# CYAN_EVSE_Logic_board_v1_0.net
KiCad netlist of a schematic drawn in Altium Designer
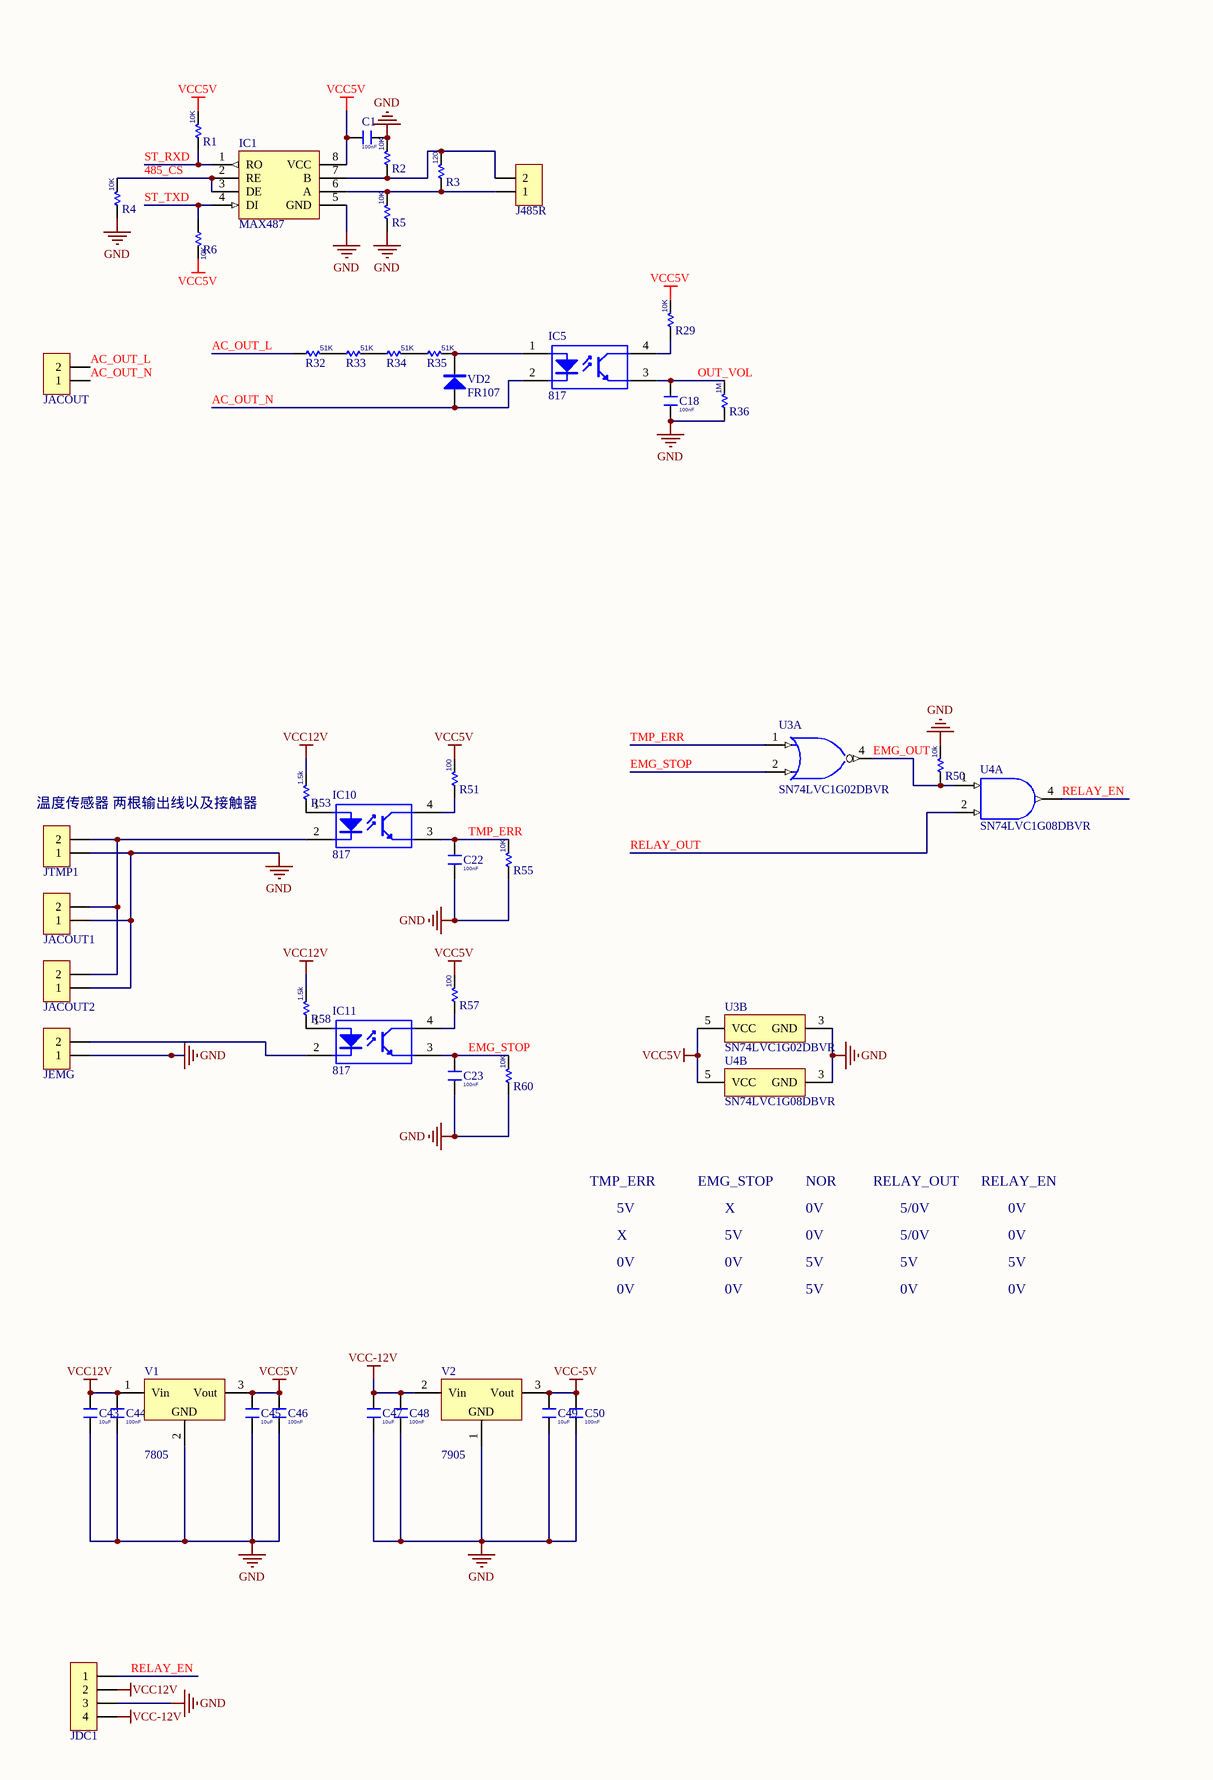
[diagram p0: CYAN_EVSE_Logic_board_v1.0.SchDoc, left]
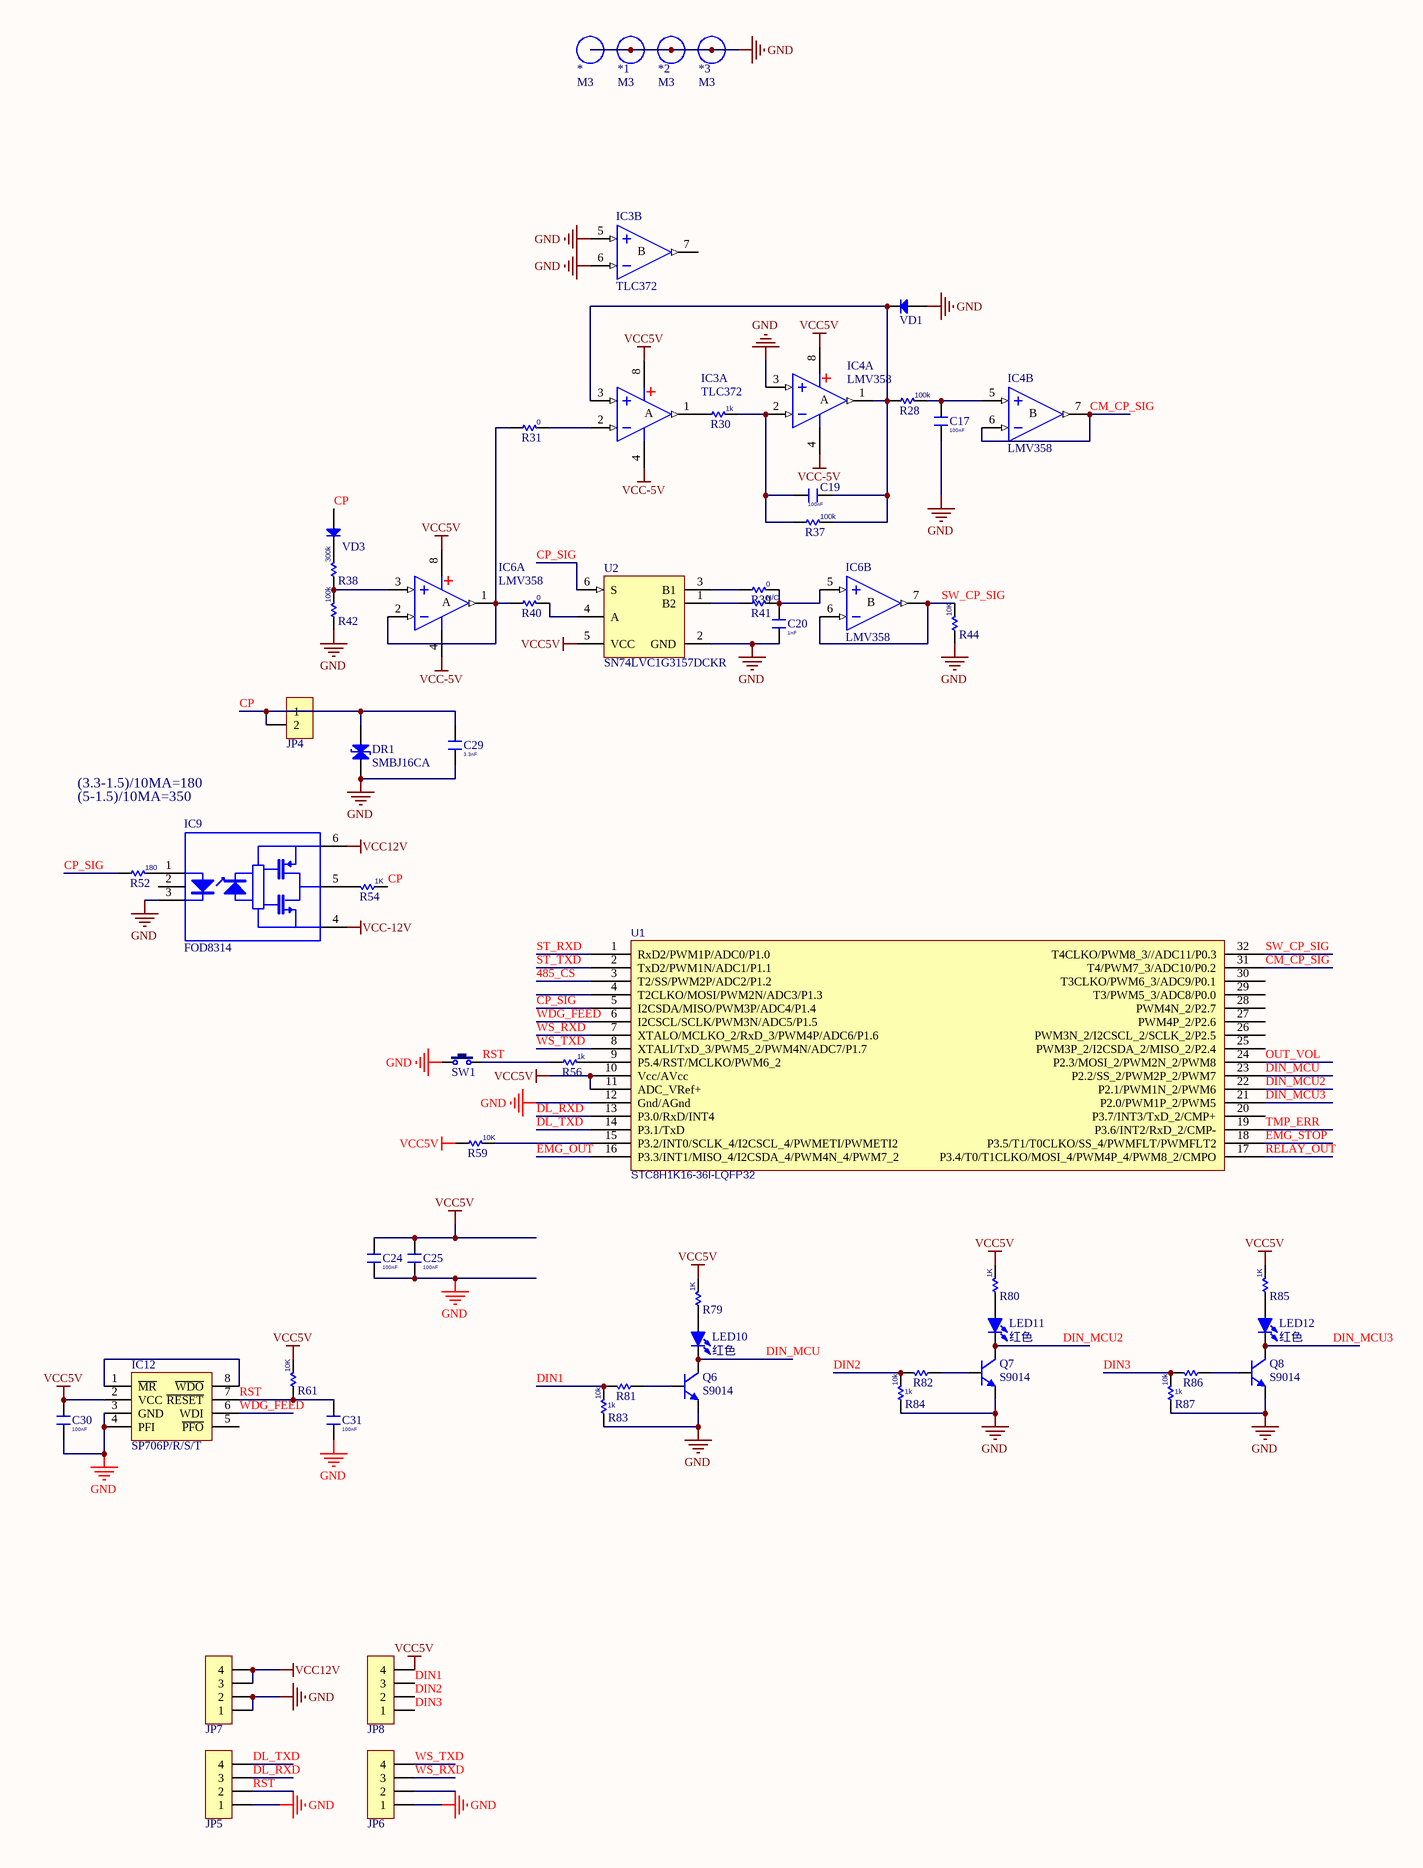
[diagram p1: CYAN_EVSE_Logic_board_v1.0.SchDoc, right]

(export (version "E")
  (design (tool "Eeschema 10.0.6"))
  (components
    (comp (ref "*")
      (value "M3")
      (footprint "M3 125X300")
      (description "铜柱孔")
      (libsource (lib "未分类器件") (part "M3"))
    )
    (comp (ref "*1")
      (value "M3")
      (footprint "M3 125X300")
      (description "铜柱孔")
      (libsource (lib "未分类器件") (part "M3"))
    )
    (comp (ref "*2")
      (value "M3")
      (footprint "M3 125X300")
      (description "铜柱孔")
      (libsource (lib "未分类器件") (part "M3"))
    )
    (comp (ref "*3")
      (value "M3")
      (footprint "M3 125X300")
      (description "铜柱孔")
      (libsource (lib "未分类器件") (part "M3"))
    )
    (comp (ref "C1")
      (value "100nF")
      (footprint "C 0805")
      (description "无极性贴片电容")
      (fields (field (name "VOLTAGE") "20V") (field (name "Comment") "C"))
      (libsource (lib "电阻-电容-电感") (part "C"))
    )
    (comp (ref "C17")
      (value "100nF")
      (footprint "C 0805")
      (description "无极性贴片电容")
      (fields (field (name "VOLTAGE") "20V") (field (name "Comment") "C"))
      (libsource (lib "电阻-电容-电感") (part "C"))
    )
    (comp (ref "C18")
      (value "100nF")
      (footprint "C 0805")
      (description "无极性贴片电容")
      (fields (field (name "VOLTAGE") "20V") (field (name "Comment") "C"))
      (libsource (lib "电阻-电容-电感") (part "C"))
    )
    (comp (ref "C19")
      (value "100nF")
      (footprint "C 0805")
      (description "无极性贴片电容")
      (fields (field (name "VOLTAGE") "20V") (field (name "Comment") "C"))
      (libsource (lib "电阻-电容-电感") (part "C"))
    )
    (comp (ref "C20")
      (value "1nF")
      (footprint "C 0805")
      (description "无极性贴片电容")
      (fields (field (name "VOLTAGE") "20V") (field (name "Comment") "C"))
      (libsource (lib "电阻-电容-电感") (part "C"))
    )
    (comp (ref "C22")
      (value "100nF")
      (footprint "C 0805")
      (description "无极性贴片电容")
      (fields (field (name "VOLTAGE") "20V") (field (name "Comment") "C"))
      (libsource (lib "电阻-电容-电感") (part "C"))
    )
    (comp (ref "C23")
      (value "100nF")
      (footprint "C 0805")
      (description "无极性贴片电容")
      (fields (field (name "VOLTAGE") "20V") (field (name "Comment") "C"))
      (libsource (lib "电阻-电容-电感") (part "C"))
    )
    (comp (ref "C24")
      (value "100nF")
      (footprint "C 0805")
      (description "无极性贴片电容")
      (fields (field (name "VOLTAGE") "20V") (field (name "Comment") "C"))
      (libsource (lib "电阻-电容-电感") (part "C"))
    )
    (comp (ref "C25")
      (value "100nF")
      (footprint "C 0805")
      (description "无极性贴片电容")
      (fields (field (name "VOLTAGE") "20V") (field (name "Comment") "C"))
      (libsource (lib "电阻-电容-电感") (part "C"))
    )
    (comp (ref "C29")
      (value "3.3nF")
      (footprint "C 1206")
      (description "无极性贴片电容")
      (fields (field (name "VOLTAGE") "50V") (field (name "Comment") "C"))
      (libsource (lib "电阻-电容-电感") (part "C"))
    )
    (comp (ref "C30")
      (value "100nF")
      (footprint "C 0805")
      (description "无极性贴片电容")
      (fields (field (name "VOLTAGE") "20V") (field (name "Comment") "C"))
      (libsource (lib "电阻-电容-电感") (part "C"))
    )
    (comp (ref "C31")
      (value "100nF")
      (footprint "C 0805")
      (description "无极性贴片电容")
      (fields (field (name "VOLTAGE") "20V") (field (name "Comment") "C"))
      (libsource (lib "电阻-电容-电感") (part "C"))
    )
    (comp (ref "C43")
      (value "10uF")
      (footprint "C 0805")
      (description "无极性贴片电容")
      (fields (field (name "VOLTAGE") "50V") (field (name "Comment") "C"))
      (libsource (lib "电阻-电容-电感") (part "C"))
    )
    (comp (ref "C44")
      (value "100nF")
      (footprint "C 0805")
      (description "无极性贴片电容")
      (fields (field (name "VOLTAGE") "50V") (field (name "Comment") "C"))
      (libsource (lib "电阻-电容-电感") (part "C"))
    )
    (comp (ref "C45")
      (value "10uF")
      (footprint "C 0805")
      (description "无极性贴片电容")
      (fields (field (name "VOLTAGE") "50V") (field (name "Comment") "C"))
      (libsource (lib "电阻-电容-电感") (part "C"))
    )
    (comp (ref "C46")
      (value "100nF")
      (footprint "C 0805")
      (description "无极性贴片电容")
      (fields (field (name "VOLTAGE") "50V") (field (name "Comment") "C"))
      (libsource (lib "电阻-电容-电感") (part "C"))
    )
    (comp (ref "C47")
      (value "10uF")
      (footprint "C 0805")
      (description "无极性贴片电容")
      (fields (field (name "VOLTAGE") "50V") (field (name "Comment") "C"))
      (libsource (lib "电阻-电容-电感") (part "C"))
    )
    (comp (ref "C48")
      (value "100nF")
      (footprint "C 0805")
      (description "无极性贴片电容")
      (fields (field (name "VOLTAGE") "50V") (field (name "Comment") "C"))
      (libsource (lib "电阻-电容-电感") (part "C"))
    )
    (comp (ref "C49")
      (value "10uF")
      (footprint "C 0805")
      (description "无极性贴片电容")
      (fields (field (name "VOLTAGE") "50V") (field (name "Comment") "C"))
      (libsource (lib "电阻-电容-电感") (part "C"))
    )
    (comp (ref "C50")
      (value "100nF")
      (footprint "C 0805")
      (description "无极性贴片电容")
      (fields (field (name "VOLTAGE") "50V") (field (name "Comment") "C"))
      (libsource (lib "电阻-电容-电感") (part "C"))
    )
    (comp (ref "DR1")
      (value "SMBJ16CA")
      (footprint "SMB")
      (description "瞬态电压抑制二极管")
      (libsource (lib "二极管-整流桥") (part "DR"))
    )
    (comp (ref "IC1")
      (value "MAX487")
      (footprint "SOP8_N")
      (description "RS485总线收发芯片")
      (libsource (lib "IC芯片") (part "MAX487"))
    )
    (comp (ref "IC3")
      (value "TLC372")
      (footprint "SOP8_L")
      (description "双路电压比较,MOS下臂输出")
      (libsource (lib "IC芯片") (part "TLC372"))
    )
    (comp (ref "IC4")
      (value "LMV358")
      (footprint "SOP8_N")
      (description "双路运放")
      (libsource (lib "IC芯片") (part "LM358"))
    )
    (comp (ref "IC5")
      (value "817")
      (footprint "SOP4-W2.54_M")
      (description "线性光耦")
      (libsource (lib "传感元件") (part "817"))
    )
    (comp (ref "IC6")
      (value "LMV358")
      (footprint "SOP8_N")
      (description "双路运放")
      (libsource (lib "IC芯片") (part "LM358"))
    )
    (comp (ref "IC9")
      (value "FOD8314")
      (footprint "SOP6_L")
      (description "MOSFET/IGBT 驱动光耦，15-30v 1a")
      (libsource (lib "传感元件") (part "FOD8314"))
    )
    (comp (ref "IC10")
      (value "817")
      (footprint "SOP4-W2.54_M")
      (description "线性光耦")
      (libsource (lib "传感元件") (part "817"))
    )
    (comp (ref "IC11")
      (value "817")
      (footprint "SOP4-W2.54_M")
      (description "线性光耦")
      (libsource (lib "传感元件") (part "817"))
    )
    (comp (ref "IC12")
      (value "SP706P/R/S/T")
      (footprint "SOP8_N")
      (description "处理器监控芯片")
      (libsource (lib "IC芯片") (part "SP706"))
    )
    (comp (ref "J485R")
      (value "HDR-1X2")
      (footprint "MC 1,5/ 2-G-3,81")
      (description "2P接插件")
      (libsource (lib "接插件") (part "Header 2"))
    )
    (comp (ref "JACOUT")
      (value "HDR-1X2")
      (footprint "MC 1,5/ 2-G-3,81")
      (description "2P接插件")
      (libsource (lib "") (part "Header 2_1"))
    )
    (comp (ref "JACOUT1")
      (value "HDR-1X2")
      (footprint "MC 1,5/ 2-G-3,81")
      (description "2P接插件")
      (libsource (lib "") (part "Header 2_1"))
    )
    (comp (ref "JACOUT2")
      (value "HDR-1X2")
      (footprint "MC 1,5/ 2-G-3,81")
      (description "2P接插件")
      (libsource (lib "") (part "Header 2_1"))
    )
    (comp (ref "JDC1")
      (value "HDR-1X4")
      (footprint "MC 1,5/ 4-G-3,81")
      (description "4P接插件")
      (libsource (lib "") (part "Header 4_1"))
    )
    (comp (ref "JEMG")
      (value "HDR-1X2")
      (footprint "MC 1,5/ 2-G-3,81")
      (description "2P接插件")
      (libsource (lib "") (part "Header 2_1"))
    )
    (comp (ref "JP4")
      (value "HDR-1X2")
      (footprint "MC 1,5/ 2-G-3,81")
      (description "2P接插件")
      (libsource (lib "") (part "Header 2_2"))
    )
    (comp (ref "JP5")
      (value "HDR-1X4")
      (footprint "HDR-1X4")
      (description "4P接插件")
      (libsource (lib "接插件") (part "Header 4"))
    )
    (comp (ref "JP6")
      (value "HDR-1X4")
      (footprint "MC 1,5/ 4-G-3,81")
      (description "4P接插件")
      (libsource (lib "接插件") (part "Header 4"))
    )
    (comp (ref "JP7")
      (value "HDR-1X4")
      (footprint "MC 1,5/ 4-G-3,81")
      (description "4P接插件")
      (libsource (lib "接插件") (part "Header 4"))
    )
    (comp (ref "JP8")
      (value "HDR-1X4")
      (footprint "MC 1,5/ 4-G-3,81")
      (description "4P接插件")
      (libsource (lib "接插件") (part "Header 4"))
    )
    (comp (ref "JTMP1")
      (value "HDR-1X2")
      (footprint "MC 1,5/ 2-G-3,81")
      (description "2P接插件")
      (libsource (lib "") (part "Header 2_1"))
    )
    (comp (ref "LED10")
      (value "红色")
      (footprint "LED 0805G")
      (description "贴片LED")
      (libsource (lib "LED") (part "LED-SMD"))
    )
    (comp (ref "LED11")
      (value "红色")
      (footprint "LED 0805G")
      (description "贴片LED")
      (libsource (lib "LED") (part "LED-SMD"))
    )
    (comp (ref "LED12")
      (value "红色")
      (footprint "LED 0805G")
      (description "贴片LED")
      (libsource (lib "LED") (part "LED-SMD"))
    )
    (comp (ref "Q6")
      (value "S9014")
      (footprint "SOT23-3N")
      (description "低噪放大-NPN型")
      (libsource (lib "三极管") (part "9014-SMD"))
    )
    (comp (ref "Q7")
      (value "S9014")
      (footprint "SOT23-3N")
      (description "低噪放大-NPN型")
      (libsource (lib "三极管") (part "9014-SMD"))
    )
    (comp (ref "Q8")
      (value "S9014")
      (footprint "SOT23-3N")
      (description "低噪放大-NPN型")
      (libsource (lib "三极管") (part "9014-SMD"))
    )
    (comp (ref "R1")
      (value "10K")
      (footprint "R 0805")
      (description "贴片电阻")
      (fields (field (name "Comment") "R"))
      (libsource (lib "电阻-电容-电感") (part "R"))
    )
    (comp (ref "R2")
      (value "10K")
      (footprint "R 0805")
      (description "贴片电阻")
      (fields (field (name "Comment") "R"))
      (libsource (lib "电阻-电容-电感") (part "R"))
    )
    (comp (ref "R3")
      (value "120")
      (footprint "R 1206")
      (description "贴片电阻")
      (fields (field (name "Comment") "R"))
      (libsource (lib "电阻-电容-电感") (part "R"))
    )
    (comp (ref "R4")
      (value "10K")
      (footprint "R 0805")
      (description "贴片电阻")
      (fields (field (name "Comment") "R"))
      (libsource (lib "电阻-电容-电感") (part "R"))
    )
    (comp (ref "R5")
      (value "10K")
      (footprint "R 0805")
      (description "贴片电阻")
      (fields (field (name "Comment") "R"))
      (libsource (lib "电阻-电容-电感") (part "R"))
    )
    (comp (ref "R6")
      (value "10K")
      (footprint "R 0805")
      (description "贴片电阻")
      (fields (field (name "Comment") "R"))
      (libsource (lib "电阻-电容-电感") (part "R"))
    )
    (comp (ref "R28")
      (value "100k")
      (footprint "R 0805")
      (description "贴片电阻")
      (fields (field (name "Comment") "R"))
      (libsource (lib "电阻-电容-电感") (part "R"))
    )
    (comp (ref "R29")
      (value "10K")
      (footprint "R 0805")
      (description "贴片电阻")
      (fields (field (name "Comment") "R"))
      (libsource (lib "电阻-电容-电感") (part "R"))
    )
    (comp (ref "R30")
      (value "1k")
      (footprint "R 0805")
      (description "贴片电阻")
      (fields (field (name "Comment") "R"))
      (libsource (lib "电阻-电容-电感") (part "R"))
    )
    (comp (ref "R31")
      (value "0")
      (footprint "R 0805")
      (description "贴片电阻")
      (fields (field (name "Comment") "R"))
      (libsource (lib "电阻-电容-电感") (part "R"))
    )
    (comp (ref "R32")
      (value "51K")
      (footprint "R 1206")
      (description "贴片电阻")
      (fields (field (name "Comment") "R"))
      (libsource (lib "电阻-电容-电感") (part "R"))
    )
    (comp (ref "R33")
      (value "51K")
      (footprint "R 1206")
      (description "贴片电阻")
      (fields (field (name "Comment") "R"))
      (libsource (lib "电阻-电容-电感") (part "R"))
    )
    (comp (ref "R34")
      (value "51K")
      (footprint "R 1206")
      (description "贴片电阻")
      (fields (field (name "Comment") "R"))
      (libsource (lib "电阻-电容-电感") (part "R"))
    )
    (comp (ref "R35")
      (value "51K")
      (footprint "R 1206")
      (description "贴片电阻")
      (fields (field (name "Comment") "R"))
      (libsource (lib "电阻-电容-电感") (part "R"))
    )
    (comp (ref "R36")
      (value "1M")
      (footprint "R 0805")
      (description "贴片电阻")
      (fields (field (name "Comment") "R"))
      (libsource (lib "电阻-电容-电感") (part "R"))
    )
    (comp (ref "R37")
      (value "100k")
      (footprint "R 0805")
      (description "贴片电阻")
      (fields (field (name "Comment") "R"))
      (libsource (lib "电阻-电容-电感") (part "R"))
    )
    (comp (ref "R38")
      (value "300k")
      (footprint "R 0805")
      (description "贴片电阻")
      (fields (field (name "Comment") "R"))
      (libsource (lib "电阻-电容-电感") (part "R"))
    )
    (comp (ref "R39")
      (value "0")
      (footprint "R 0805")
      (description "贴片电阻")
      (fields (field (name "Comment") "R"))
      (libsource (lib "电阻-电容-电感") (part "R"))
    )
    (comp (ref "R40")
      (value "0")
      (footprint "R 0805")
      (description "贴片电阻")
      (fields (field (name "Comment") "R"))
      (libsource (lib "电阻-电容-电感") (part "R"))
    )
    (comp (ref "R41")
      (value "N/C")
      (footprint "R 0805")
      (description "贴片电阻")
      (fields (field (name "Comment") "R"))
      (libsource (lib "电阻-电容-电感") (part "R"))
    )
    (comp (ref "R42")
      (value "100k")
      (footprint "R 0805")
      (description "贴片电阻")
      (fields (field (name "Comment") "R"))
      (libsource (lib "电阻-电容-电感") (part "R"))
    )
    (comp (ref "R44")
      (value "10K")
      (footprint "R 0805")
      (description "贴片电阻")
      (fields (field (name "Comment") "R"))
      (libsource (lib "电阻-电容-电感") (part "R"))
    )
    (comp (ref "R50")
      (value "10k")
      (footprint "R 0805")
      (description "贴片电阻")
      (fields (field (name "Comment") "R"))
      (libsource (lib "电阻-电容-电感") (part "R"))
    )
    (comp (ref "R51")
      (value "100")
      (footprint "R 0805")
      (description "贴片电阻")
      (fields (field (name "Comment") "R"))
      (libsource (lib "电阻-电容-电感") (part "R"))
    )
    (comp (ref "R52")
      (value "180")
      (footprint "R 0805")
      (description "贴片电阻")
      (fields (field (name "Comment") "R"))
      (libsource (lib "电阻-电容-电感") (part "R"))
    )
    (comp (ref "R53")
      (value "1.5k")
      (footprint "R 0805")
      (description "贴片电阻")
      (fields (field (name "Comment") "R"))
      (libsource (lib "电阻-电容-电感") (part "R"))
    )
    (comp (ref "R54")
      (value "1K")
      (footprint "R 1206")
      (description "贴片电阻")
      (fields (field (name "Comment") "R"))
      (libsource (lib "电阻-电容-电感") (part "R"))
    )
    (comp (ref "R55")
      (value "10K")
      (footprint "R 0805")
      (description "贴片电阻")
      (fields (field (name "Comment") "R"))
      (libsource (lib "电阻-电容-电感") (part "R"))
    )
    (comp (ref "R56")
      (value "1k")
      (footprint "R 0805")
      (description "贴片电阻")
      (fields (field (name "Comment") "R"))
      (libsource (lib "电阻-电容-电感") (part "R"))
    )
    (comp (ref "R57")
      (value "100")
      (footprint "R 0805")
      (description "贴片电阻")
      (fields (field (name "Comment") "R"))
      (libsource (lib "电阻-电容-电感") (part "R"))
    )
    (comp (ref "R58")
      (value "1.5k")
      (footprint "R 0805")
      (description "贴片电阻")
      (fields (field (name "Comment") "R"))
      (libsource (lib "电阻-电容-电感") (part "R"))
    )
    (comp (ref "R59")
      (value "10K")
      (footprint "R 0805")
      (description "贴片电阻")
      (fields (field (name "Comment") "R"))
      (libsource (lib "电阻-电容-电感") (part "R"))
    )
    (comp (ref "R60")
      (value "10K")
      (footprint "R 0805")
      (description "贴片电阻")
      (fields (field (name "Comment") "R"))
      (libsource (lib "电阻-电容-电感") (part "R"))
    )
    (comp (ref "R61")
      (value "10K")
      (footprint "R 0805")
      (description "贴片电阻")
      (fields (field (name "Comment") "R"))
      (libsource (lib "电阻-电容-电感") (part "R"))
    )
    (comp (ref "R79")
      (value "1K")
      (footprint "R 0805")
      (description "贴片电阻")
      (fields (field (name "Comment") "R"))
      (libsource (lib "电阻-电容-电感") (part "R"))
    )
    (comp (ref "R80")
      (value "1K")
      (footprint "R 0805")
      (description "贴片电阻")
      (fields (field (name "Comment") "R"))
      (libsource (lib "电阻-电容-电感") (part "R"))
    )
    (comp (ref "R81")
      (value "1k")
      (footprint "R 0805")
      (description "贴片电阻")
      (fields (field (name "Comment") "R"))
      (libsource (lib "电阻-电容-电感") (part "R"))
    )
    (comp (ref "R82")
      (value "1k")
      (footprint "R 0805")
      (description "贴片电阻")
      (fields (field (name "Comment") "R"))
      (libsource (lib "电阻-电容-电感") (part "R"))
    )
    (comp (ref "R83")
      (value "10k")
      (footprint "R 0805")
      (description "贴片电阻")
      (fields (field (name "Comment") "R"))
      (libsource (lib "电阻-电容-电感") (part "R"))
    )
    (comp (ref "R84")
      (value "10k")
      (footprint "R 0805")
      (description "贴片电阻")
      (fields (field (name "Comment") "R"))
      (libsource (lib "电阻-电容-电感") (part "R"))
    )
    (comp (ref "R85")
      (value "1K")
      (footprint "R 0805")
      (description "贴片电阻")
      (fields (field (name "Comment") "R"))
      (libsource (lib "电阻-电容-电感") (part "R"))
    )
    (comp (ref "R86")
      (value "1k")
      (footprint "R 0805")
      (description "贴片电阻")
      (fields (field (name "Comment") "R"))
      (libsource (lib "电阻-电容-电感") (part "R"))
    )
    (comp (ref "R87")
      (value "10k")
      (footprint "R 0805")
      (description "贴片电阻")
      (fields (field (name "Comment") "R"))
      (libsource (lib "电阻-电容-电感") (part "R"))
    )
    (comp (ref "SW1") (value "NC") (footprint "TSW SMD-3*6*2.5") (libsource (lib "按键-开关") (part "TSW 3x6")))
    (comp (ref "U1")
      (value "STC8H1K16-36I-LQFP32")
      (footprint "LQFP32 7X7_N")
      (libsource (lib "STC系列单片机") (part "STC8H1K16-36I-LQFP32"))
    )
    (comp (ref "U2")
      (value "SN74LVC1G3157DCKR")
      (footprint "DCK0006A_N")
      (description "Single-Pole, Double-Throw Analog Switch, DCK0006A, LARGE T&R")
      (fields
        (field (name "GENERIC PART NUMBER") "SN74LVC1G3157")
        (field (name "MANUFACTURER") "Texas Instruments")
      )
      (libsource (lib "TI_Logic_Little_Logic") (part "SN74LVC1G3157DCKR"))
    )
    (comp (ref "U3")
      (value "SN74LVC1G02DBVR")
      (footprint "DBV0005A_N")
      (description "Single 2-Input Positive-NOR Gate, DBV0005A, LARGE T&R")
      (fields
        (field (name "GENERIC PART NUMBER") "SN74LVC1G02")
        (field (name "MANUFACTURER") "Texas Instruments")
      )
      (libsource (lib "TI_Logic_Little_Logic") (part "SN74LVC1G02DBVR"))
    )
    (comp (ref "U4")
      (value "SN74LVC1G08DBVR")
      (footprint "DBV0005A_N")
      (description "Single 2-Input Positive-AND Gate, DBV0005A, LARGE T&R")
      (fields
        (field (name "GENERIC PART NUMBER") "SN74LVC1G08")
        (field (name "MANUFACTURER") "Texas Instruments")
      )
      (libsource (lib "TI_Logic_Little_Logic") (part "SN74LVC1G08DBVR"))
    )
    (comp (ref "V1")
      (value "7805")
      (footprint "TO252")
      (description "线性稳压芯片")
      (libsource (lib "IC芯片") (part "78xx"))
    )
    (comp (ref "V2")
      (value "7905")
      (footprint "TO252")
      (description "线性稳压芯片")
      (libsource (lib "IC芯片") (part "79xx"))
    )
    (comp (ref "VD1")
      (value "1N4148")
      (footprint "SOD-323")
      (description "高速开关二极管")
      (libsource (lib "二极管-整流桥") (part "1N4148"))
    )
    (comp (ref "VD2")
      (value "FR107")
      (footprint "SOD-123")
      (description "快恢复整流二极管")
      (libsource (lib "二极管-整流桥") (part "FR107"))
    )
    (comp (ref "VD3")
      (value "1N4148")
      (footprint "SOD-323")
      (description "高速开关二极管")
      (libsource (lib "二极管-整流桥") (part "1N4148"))
    )
  )
  (nets
    (net (code "1") (name "/485_CS") (class "Default")
      (node (ref "IC1") (pin "2") (pinfunction "RE_2") (pintype "passive"))
      (node (ref "IC1") (pin "3") (pinfunction "DE_3") (pintype "passive"))
      (node (ref "R4") (pin "2") (pinfunction "2_2") (pintype "passive"))
      (node (ref "U1") (pin "3") (pinfunction "T2/SS/PWM2P/ADC2/P1.2_3") (pintype "passive"))
    )
    (net (code "2") (name "/AC_OUT_L") (class "Default")
      (node (ref "JACOUT") (pin "2") (pinfunction "2_2") (pintype "passive"))
      (node (ref "R32") (pin "1") (pinfunction "1_1") (pintype "passive"))
    )
    (net (code "3") (name "/AC_OUT_N") (class "Default")
      (node (ref "IC5") (pin "2") (pinfunction "K_2") (pintype "passive"))
      (node (ref "JACOUT") (pin "1") (pinfunction "1_1") (pintype "passive"))
      (node (ref "VD2") (pin "1") (pinfunction "A_1") (pintype "passive"))
    )
    (net (code "4") (name "/CM_CP_SIG") (class "Default")
      (node (ref "IC4") (pin "6") (pinfunction "IN-_6") (pintype "input"))
      (node (ref "IC4") (pin "7") (pinfunction "OUT_7") (pintype "output"))
      (node (ref "U1") (pin "31") (pinfunction "T4/PWM7_3/ADC10/P0.2_31") (pintype "passive"))
    )
    (net (code "5") (name "/CP") (class "Default")
      (node (ref "C29") (pin "2") (pinfunction "2_2") (pintype "passive"))
      (node (ref "DR1") (pin "1") (pinfunction "A_1") (pintype "passive"))
      (node (ref "JP4") (pin "1") (pinfunction "1_1") (pintype "passive"))
      (node (ref "JP4") (pin "2") (pinfunction "2_2") (pintype "passive"))
      (node (ref "R54") (pin "1") (pinfunction "1_1") (pintype "passive"))
      (node (ref "VD3") (pin "1") (pinfunction "A_1") (pintype "passive"))
    )
    (net (code "6") (name "/CP_SIG") (class "Default")
      (node (ref "R52") (pin "1") (pinfunction "1_1") (pintype "passive"))
      (node (ref "U1") (pin "5") (pinfunction "I2CSDA/MISO/PWM3P/ADC4/P1.4_5") (pintype "passive"))
      (node (ref "U2") (pin "6") (pinfunction "S_6") (pintype "input"))
    )
    (net (code "7") (name "/DIN1") (class "Default")
      (node (ref "JP8") (pin "3") (pinfunction "3_3") (pintype "passive"))
      (node (ref "R81") (pin "2") (pinfunction "2_2") (pintype "passive"))
      (node (ref "R83") (pin "2") (pinfunction "2_2") (pintype "passive"))
    )
    (net (code "8") (name "/DIN2") (class "Default")
      (node (ref "JP8") (pin "2") (pinfunction "2_2") (pintype "passive"))
      (node (ref "R82") (pin "2") (pinfunction "2_2") (pintype "passive"))
      (node (ref "R84") (pin "2") (pinfunction "2_2") (pintype "passive"))
    )
    (net (code "9") (name "/DIN3") (class "Default")
      (node (ref "JP8") (pin "1") (pinfunction "1_1") (pintype "passive"))
      (node (ref "R86") (pin "2") (pinfunction "2_2") (pintype "passive"))
      (node (ref "R87") (pin "2") (pinfunction "2_2") (pintype "passive"))
    )
    (net (code "10") (name "/DIN_MCU") (class "Default")
      (node (ref "LED10") (pin "2") (pinfunction "K_2") (pintype "passive"))
      (node (ref "Q6") (pin "3") (pinfunction "C_3") (pintype "passive"))
      (node (ref "U1") (pin "23") (pinfunction "P2.2/SS_2/PWM2P_2/PWM7_23") (pintype "passive"))
    )
    (net (code "11") (name "/DIN_MCU2") (class "Default")
      (node (ref "LED11") (pin "2") (pinfunction "K_2") (pintype "passive"))
      (node (ref "Q7") (pin "3") (pinfunction "C_3") (pintype "passive"))
      (node (ref "U1") (pin "22") (pinfunction "P2.1/PWM1N_2/PWM6_22") (pintype "passive"))
    )
    (net (code "12") (name "/DIN_MCU3") (class "Default")
      (node (ref "LED12") (pin "2") (pinfunction "K_2") (pintype "passive"))
      (node (ref "Q8") (pin "3") (pinfunction "C_3") (pintype "passive"))
      (node (ref "U1") (pin "21") (pinfunction "P2.0/PWM1P_2/PWM5_21") (pintype "passive"))
    )
    (net (code "13") (name "/DL_RXD") (class "Default")
      (node (ref "JP5") (pin "3") (pinfunction "3_3") (pintype "passive"))
      (node (ref "U1") (pin "13") (pinfunction "P3.0/RxD/INT4_13") (pintype "passive"))
    )
    (net (code "14") (name "/DL_TXD") (class "Default")
      (node (ref "JP5") (pin "4") (pinfunction "4_4") (pintype "passive"))
      (node (ref "U1") (pin "14") (pinfunction "P3.1/TxD_14") (pintype "passive"))
    )
    (net (code "15") (name "/EMG_OUT") (class "Default")
      (node (ref "R50") (pin "1") (pinfunction "1_1") (pintype "passive"))
      (node (ref "U1") (pin "16") (pinfunction "P3.3/INT1/MISO_4/I2CSDA_4/PWM4N_4/PWM7_2_16") (pintype "passive"))
      (node (ref "U3") (pin "4") (pinfunction "Y_4") (pintype "output"))
      (node (ref "U4") (pin "1") (pinfunction "A_1") (pintype "input"))
    )
    (net (code "16") (name "/EMG_STOP") (class "Default")
      (node (ref "C23") (pin "2") (pinfunction "2_2") (pintype "passive"))
      (node (ref "IC11") (pin "3") (pinfunction "E_3") (pintype "passive"))
      (node (ref "R60") (pin "2") (pinfunction "2_2") (pintype "passive"))
      (node (ref "U1") (pin "18") (pinfunction "P3.5/T1/T0CLKO/SS_4/PWMFLT/PWMFLT2_18") (pintype "passive"))
      (node (ref "U3") (pin "2") (pinfunction "B_2") (pintype "input"))
    )
    (net (code "17") (name "/OUT_VOL") (class "Default")
      (node (ref "C18") (pin "2") (pinfunction "2_2") (pintype "passive"))
      (node (ref "IC5") (pin "3") (pinfunction "E_3") (pintype "passive"))
      (node (ref "R36") (pin "2") (pinfunction "2_2") (pintype "passive"))
      (node (ref "U1") (pin "24") (pinfunction "P2.3/MOSI_2/PWM2N_2/PWM8_24") (pintype "passive"))
    )
    (net (code "18") (name "/RELAY_EN") (class "Default")
      (node (ref "JDC1") (pin "1") (pinfunction "1_1") (pintype "passive"))
      (node (ref "U4") (pin "4") (pinfunction "Y_4") (pintype "output"))
    )
    (net (code "19") (name "/RELAY_OUT") (class "Default")
      (node (ref "U1") (pin "17") (pinfunction "P3.4/T0/T1CLKO/MOSI_4/PWM4P_4/PWM8_2/CMPO_17") (pintype "passive"))
      (node (ref "U4") (pin "2") (pinfunction "B_2") (pintype "input"))
    )
    (net (code "20") (name "/RST") (class "Default")
      (node (ref "C31") (pin "2") (pinfunction "2_2") (pintype "passive"))
      (node (ref "IC12") (pin "7") (pinfunction "~{RESET}_7") (pintype "passive"))
      (node (ref "JP5") (pin "2") (pinfunction "2_2") (pintype "passive"))
      (node (ref "R56") (pin "1") (pinfunction "1_1") (pintype "passive"))
      (node (ref "R61") (pin "1") (pinfunction "1_1") (pintype "passive"))
      (node (ref "SW1") (pin "2") (pinfunction "2_2") (pintype "passive"))
    )
    (net (code "21") (name "/ST_RXD") (class "Default")
      (node (ref "IC1") (pin "1") (pinfunction "RO_1") (pintype "output"))
      (node (ref "R1") (pin "1") (pinfunction "1_1") (pintype "passive"))
      (node (ref "U1") (pin "1") (pinfunction "RxD2/PWM1P/ADC0/P1.0_1") (pintype "passive"))
    )
    (net (code "22") (name "/ST_TXD") (class "Default")
      (node (ref "IC1") (pin "4") (pinfunction "DI_4") (pintype "input"))
      (node (ref "R6") (pin "1") (pinfunction "1_1") (pintype "passive"))
      (node (ref "U1") (pin "2") (pinfunction "TxD2/PWM1N/ADC1/P1.1_2") (pintype "passive"))
    )
    (net (code "23") (name "/SW_CP_SIG") (class "Default")
      (node (ref "IC6") (pin "6") (pinfunction "IN-_6") (pintype "input"))
      (node (ref "IC6") (pin "7") (pinfunction "OUT_7") (pintype "output"))
      (node (ref "R44") (pin "2") (pinfunction "2_2") (pintype "passive"))
      (node (ref "U1") (pin "32") (pinfunction "T4CLKO/PWM8_3//ADC11/P0.3_32") (pintype "passive"))
    )
    (net (code "24") (name "/TMP_ERR") (class "Default")
      (node (ref "C22") (pin "2") (pinfunction "2_2") (pintype "passive"))
      (node (ref "IC10") (pin "3") (pinfunction "E_3") (pintype "passive"))
      (node (ref "R55") (pin "2") (pinfunction "2_2") (pintype "passive"))
      (node (ref "U1") (pin "19") (pinfunction "P3.6/INT2/RxD_2/CMP-_19") (pintype "passive"))
      (node (ref "U3") (pin "1") (pinfunction "A_1") (pintype "input"))
    )
    (net (code "25") (name "/WDG_FEED") (class "Default")
      (node (ref "IC12") (pin "6") (pinfunction "WDI_6") (pintype "passive"))
      (node (ref "U1") (pin "6") (pinfunction "I2CSCL/SCLK/PWM3N/ADC5/P1.5_6") (pintype "passive"))
    )
    (net (code "26") (name "/WS_RXD") (class "Default")
      (node (ref "JP6") (pin "3") (pinfunction "3_3") (pintype "passive"))
      (node (ref "U1") (pin "7") (pinfunction "XTALO/MCLKO_2/RxD_3/PWM4P/ADC6/P1.6_7") (pintype "passive"))
    )
    (net (code "27") (name "/WS_TXD") (class "Default")
      (node (ref "JP6") (pin "4") (pinfunction "4_4") (pintype "passive"))
      (node (ref "U1") (pin "8") (pinfunction "XTALI/TxD_3/PWM5_2/PWM4N/ADC7/P1.7_8") (pintype "passive"))
    )
    (net (code "28") (name "GND") (class "Default")
      (node (ref "*") (pin "0") (pinfunction "0_0") (pintype "passive"))
      (node (ref "*1") (pin "0") (pinfunction "0_0") (pintype "passive"))
      (node (ref "*2") (pin "0") (pinfunction "0_0") (pintype "passive"))
      (node (ref "*3") (pin "0") (pinfunction "0_0") (pintype "passive"))
      (node (ref "C1") (pin "1") (pinfunction "1_1") (pintype "passive"))
      (node (ref "C17") (pin "2") (pinfunction "2_2") (pintype "passive"))
      (node (ref "C18") (pin "1") (pinfunction "1_1") (pintype "passive"))
      (node (ref "C20") (pin "1") (pinfunction "1_1") (pintype "passive"))
      (node (ref "C22") (pin "1") (pinfunction "1_1") (pintype "passive"))
      (node (ref "C23") (pin "1") (pinfunction "1_1") (pintype "passive"))
      (node (ref "C24") (pin "1") (pinfunction "1_1") (pintype "passive"))
      (node (ref "C25") (pin "1") (pinfunction "1_1") (pintype "passive"))
      (node (ref "C29") (pin "1") (pinfunction "1_1") (pintype "passive"))
      (node (ref "C30") (pin "1") (pinfunction "1_1") (pintype "passive"))
      (node (ref "C31") (pin "1") (pinfunction "1_1") (pintype "passive"))
      (node (ref "C43") (pin "1") (pinfunction "1_1") (pintype "passive"))
      (node (ref "C44") (pin "1") (pinfunction "1_1") (pintype "passive"))
      (node (ref "C45") (pin "1") (pinfunction "1_1") (pintype "passive"))
      (node (ref "C46") (pin "1") (pinfunction "1_1") (pintype "passive"))
      (node (ref "C47") (pin "1") (pinfunction "1_1") (pintype "passive"))
      (node (ref "C48") (pin "1") (pinfunction "1_1") (pintype "passive"))
      (node (ref "C49") (pin "1") (pinfunction "1_1") (pintype "passive"))
      (node (ref "C50") (pin "1") (pinfunction "1_1") (pintype "passive"))
      (node (ref "DR1") (pin "2") (pinfunction "K_2") (pintype "passive"))
      (node (ref "IC1") (pin "5") (pinfunction "GND_5") (pintype "passive"))
      (node (ref "IC12") (pin "3") (pinfunction "GND_3") (pintype "passive"))
      (node (ref "IC12") (pin "4") (pinfunction "PFI_4") (pintype "passive"))
      (node (ref "IC3") (pin "5") (pinfunction "IN+_5") (pintype "input"))
      (node (ref "IC3") (pin "6") (pinfunction "IN-_6") (pintype "input"))
      (node (ref "IC4") (pin "3") (pinfunction "IN+_3") (pintype "input"))
      (node (ref "IC9") (pin "3") (pinfunction "K_3") (pintype "passive"))
      (node (ref "JACOUT1") (pin "1") (pinfunction "1_1") (pintype "passive"))
      (node (ref "JACOUT2") (pin "1") (pinfunction "1_1") (pintype "passive"))
      (node (ref "JDC1") (pin "3") (pinfunction "3_3") (pintype "passive"))
      (node (ref "JEMG") (pin "1") (pinfunction "1_1") (pintype "passive"))
      (node (ref "JP5") (pin "1") (pinfunction "1_1") (pintype "passive"))
      (node (ref "JP6") (pin "1") (pinfunction "1_1") (pintype "passive"))
      (node (ref "JP7") (pin "1") (pinfunction "1_1") (pintype "passive"))
      (node (ref "JP7") (pin "2") (pinfunction "2_2") (pintype "passive"))
      (node (ref "JTMP1") (pin "1") (pinfunction "1_1") (pintype "passive"))
      (node (ref "Q6") (pin "2") (pinfunction "E_2") (pintype "passive"))
      (node (ref "Q7") (pin "2") (pinfunction "E_2") (pintype "passive"))
      (node (ref "Q8") (pin "2") (pinfunction "E_2") (pintype "passive"))
      (node (ref "R2") (pin "2") (pinfunction "2_2") (pintype "passive"))
      (node (ref "R36") (pin "1") (pinfunction "1_1") (pintype "passive"))
      (node (ref "R4") (pin "1") (pinfunction "1_1") (pintype "passive"))
      (node (ref "R42") (pin "1") (pinfunction "1_1") (pintype "passive"))
      (node (ref "R44") (pin "1") (pinfunction "1_1") (pintype "passive"))
      (node (ref "R5") (pin "1") (pinfunction "1_1") (pintype "passive"))
      (node (ref "R50") (pin "2") (pinfunction "2_2") (pintype "passive"))
      (node (ref "R55") (pin "1") (pinfunction "1_1") (pintype "passive"))
      (node (ref "R60") (pin "1") (pinfunction "1_1") (pintype "passive"))
      (node (ref "R83") (pin "1") (pinfunction "1_1") (pintype "passive"))
      (node (ref "R84") (pin "1") (pinfunction "1_1") (pintype "passive"))
      (node (ref "R87") (pin "1") (pinfunction "1_1") (pintype "passive"))
      (node (ref "SW1") (pin "1") (pinfunction "1_1") (pintype "passive"))
      (node (ref "U1") (pin "12") (pinfunction "Gnd/AGnd_12") (pintype "passive"))
      (node (ref "U2") (pin "2") (pinfunction "GND_2") (pintype "power_in"))
      (node (ref "U3") (pin "3") (pinfunction "GND_3") (pintype "power_in"))
      (node (ref "U4") (pin "3") (pinfunction "GND_3") (pintype "power_in"))
      (node (ref "V1") (pin "2") (pinfunction "GND_2") (pintype "passive"))
      (node (ref "V2") (pin "1") (pinfunction "GND_1") (pintype "passive"))
      (node (ref "VD1") (pin "1") (pinfunction "A_1") (pintype "passive"))
    )
    (net (code "29") (name "Net-(IC1-A)") (class "Default")
      (node (ref "IC1") (pin "6") (pinfunction "A_6") (pintype "passive"))
      (node (ref "J485R") (pin "1") (pinfunction "1_1") (pintype "passive"))
      (node (ref "R3") (pin "1") (pinfunction "1_1") (pintype "passive"))
      (node (ref "R5") (pin "2") (pinfunction "2_2") (pintype "passive"))
    )
    (net (code "30") (name "Net-(IC1-B)") (class "Default")
      (node (ref "IC1") (pin "7") (pinfunction "B_7") (pintype "passive"))
      (node (ref "J485R") (pin "2") (pinfunction "2_2") (pintype "passive"))
      (node (ref "R2") (pin "1") (pinfunction "1_1") (pintype "passive"))
      (node (ref "R3") (pin "2") (pinfunction "2_2") (pintype "passive"))
    )
    (net (code "31") (name "Net-(IC3A-IN+)") (class "Default")
      (node (ref "C19") (pin "1") (pinfunction "1_1") (pintype "passive"))
      (node (ref "IC3") (pin "3") (pinfunction "IN+_3") (pintype "input"))
      (node (ref "IC4") (pin "1") (pinfunction "OUT_1") (pintype "output"))
      (node (ref "R28") (pin "1") (pinfunction "1_1") (pintype "passive"))
      (node (ref "R37") (pin "2") (pinfunction "2_2") (pintype "passive"))
      (node (ref "VD1") (pin "2") (pinfunction "K_2") (pintype "passive"))
    )
    (net (code "32") (name "Net-(IC3A-IN-)") (class "Default")
      (node (ref "IC3") (pin "2") (pinfunction "IN-_2") (pintype "input"))
      (node (ref "R31") (pin "2") (pinfunction "2_2") (pintype "passive"))
    )
    (net (code "33") (name "Net-(IC3A-OUT)") (class "Default")
      (node (ref "IC3") (pin "1") (pinfunction "OUT_1") (pintype "output"))
      (node (ref "R30") (pin "1") (pinfunction "1_1") (pintype "passive"))
    )
    (net (code "34") (name "Net-(IC4A-IN-)") (class "Default")
      (node (ref "C19") (pin "2") (pinfunction "2_2") (pintype "passive"))
      (node (ref "IC4") (pin "2") (pinfunction "IN-_2") (pintype "input"))
      (node (ref "R30") (pin "2") (pinfunction "2_2") (pintype "passive"))
      (node (ref "R37") (pin "1") (pinfunction "1_1") (pintype "passive"))
    )
    (net (code "35") (name "Net-(IC4B-IN+)") (class "Default")
      (node (ref "C17") (pin "1") (pinfunction "1_1") (pintype "passive"))
      (node (ref "IC4") (pin "5") (pinfunction "IN+_5") (pintype "input"))
      (node (ref "R28") (pin "2") (pinfunction "2_2") (pintype "passive"))
    )
    (net (code "36") (name "Net-(IC5-A)") (class "Default")
      (node (ref "IC5") (pin "1") (pinfunction "A_1") (pintype "passive"))
      (node (ref "R35") (pin "2") (pinfunction "2_2") (pintype "passive"))
      (node (ref "VD2") (pin "2") (pinfunction "K_2") (pintype "passive"))
    )
    (net (code "37") (name "Net-(IC5-C)") (class "Default")
      (node (ref "IC5") (pin "4") (pinfunction "C_4") (pintype "passive"))
      (node (ref "R29") (pin "1") (pinfunction "1_1") (pintype "passive"))
    )
    (net (code "38") (name "Net-(IC6A-IN+)") (class "Default")
      (node (ref "IC6") (pin "3") (pinfunction "IN+_3") (pintype "input"))
      (node (ref "R38") (pin "1") (pinfunction "1_1") (pintype "passive"))
      (node (ref "R42") (pin "2") (pinfunction "2_2") (pintype "passive"))
    )
    (net (code "39") (name "Net-(IC6A-IN-)") (class "Default")
      (node (ref "IC6") (pin "1") (pinfunction "OUT_1") (pintype "output"))
      (node (ref "IC6") (pin "2") (pinfunction "IN-_2") (pintype "input"))
      (node (ref "R31") (pin "1") (pinfunction "1_1") (pintype "passive"))
      (node (ref "R40") (pin "1") (pinfunction "1_1") (pintype "passive"))
    )
    (net (code "40") (name "Net-(IC6B-IN+)") (class "Default")
      (node (ref "C20") (pin "2") (pinfunction "2_2") (pintype "passive"))
      (node (ref "IC6") (pin "5") (pinfunction "IN+_5") (pintype "input"))
      (node (ref "R39") (pin "2") (pinfunction "2_2") (pintype "passive"))
      (node (ref "R41") (pin "2") (pinfunction "2_2") (pintype "passive"))
    )
    (net (code "41") (name "Net-(IC9-A)") (class "Default")
      (node (ref "IC9") (pin "1") (pinfunction "A_1") (pintype "passive"))
      (node (ref "R52") (pin "2") (pinfunction "2_2") (pintype "passive"))
    )
    (net (code "42") (name "Net-(IC9-OUT)") (class "Default")
      (node (ref "IC9") (pin "5") (pinfunction "OUT_5") (pintype "passive"))
      (node (ref "R54") (pin "2") (pinfunction "2_2") (pintype "passive"))
    )
    (net (code "43") (name "Net-(IC10-A)") (class "Default")
      (node (ref "IC10") (pin "1") (pinfunction "A_1") (pintype "passive"))
      (node (ref "R53") (pin "1") (pinfunction "1_1") (pintype "passive"))
    )
    (net (code "44") (name "Net-(IC10-C)") (class "Default")
      (node (ref "IC10") (pin "4") (pinfunction "C_4") (pintype "passive"))
      (node (ref "R51") (pin "1") (pinfunction "1_1") (pintype "passive"))
    )
    (net (code "45") (name "Net-(IC10-K)") (class "Default")
      (node (ref "IC10") (pin "2") (pinfunction "K_2") (pintype "passive"))
      (node (ref "JACOUT1") (pin "2") (pinfunction "2_2") (pintype "passive"))
      (node (ref "JACOUT2") (pin "2") (pinfunction "2_2") (pintype "passive"))
      (node (ref "JTMP1") (pin "2") (pinfunction "2_2") (pintype "passive"))
    )
    (net (code "46") (name "Net-(IC11-A)") (class "Default")
      (node (ref "IC11") (pin "1") (pinfunction "A_1") (pintype "passive"))
      (node (ref "R58") (pin "1") (pinfunction "1_1") (pintype "passive"))
    )
    (net (code "47") (name "Net-(IC11-C)") (class "Default")
      (node (ref "IC11") (pin "4") (pinfunction "C_4") (pintype "passive"))
      (node (ref "R57") (pin "1") (pinfunction "1_1") (pintype "passive"))
    )
    (net (code "48") (name "Net-(IC11-K)") (class "Default")
      (node (ref "IC11") (pin "2") (pinfunction "K_2") (pintype "passive"))
      (node (ref "JEMG") (pin "2") (pinfunction "2_2") (pintype "passive"))
    )
    (net (code "49") (name "Net-(IC12-~{MR})") (class "Default")
      (node (ref "IC12") (pin "1") (pinfunction "~{MR}_1") (pintype "passive"))
      (node (ref "IC12") (pin "8") (pinfunction "~{WDO}_8") (pintype "passive"))
    )
    (net (code "50") (name "Net-(LED10-A)") (class "Default")
      (node (ref "LED10") (pin "1") (pinfunction "A_1") (pintype "passive"))
      (node (ref "R79") (pin "1") (pinfunction "1_1") (pintype "passive"))
    )
    (net (code "51") (name "Net-(LED11-A)") (class "Default")
      (node (ref "LED11") (pin "1") (pinfunction "A_1") (pintype "passive"))
      (node (ref "R80") (pin "1") (pinfunction "1_1") (pintype "passive"))
    )
    (net (code "52") (name "Net-(LED12-A)") (class "Default")
      (node (ref "LED12") (pin "1") (pinfunction "A_1") (pintype "passive"))
      (node (ref "R85") (pin "1") (pinfunction "1_1") (pintype "passive"))
    )
    (net (code "53") (name "Net-(Q6-B)") (class "Default")
      (node (ref "Q6") (pin "1") (pinfunction "B_1") (pintype "passive"))
      (node (ref "R81") (pin "1") (pinfunction "1_1") (pintype "passive"))
    )
    (net (code "54") (name "Net-(Q7-B)") (class "Default")
      (node (ref "Q7") (pin "1") (pinfunction "B_1") (pintype "passive"))
      (node (ref "R82") (pin "1") (pinfunction "1_1") (pintype "passive"))
    )
    (net (code "55") (name "Net-(Q8-B)") (class "Default")
      (node (ref "Q8") (pin "1") (pinfunction "B_1") (pintype "passive"))
      (node (ref "R86") (pin "1") (pinfunction "1_1") (pintype "passive"))
    )
    (net (code "56") (name "Net-(R32-Pad2)") (class "Default")
      (node (ref "R32") (pin "2") (pinfunction "2_2") (pintype "passive"))
      (node (ref "R33") (pin "1") (pinfunction "1_1") (pintype "passive"))
    )
    (net (code "57") (name "Net-(R33-Pad2)") (class "Default")
      (node (ref "R33") (pin "2") (pinfunction "2_2") (pintype "passive"))
      (node (ref "R34") (pin "1") (pinfunction "1_1") (pintype "passive"))
    )
    (net (code "58") (name "Net-(R34-Pad2)") (class "Default")
      (node (ref "R34") (pin "2") (pinfunction "2_2") (pintype "passive"))
      (node (ref "R35") (pin "1") (pinfunction "1_1") (pintype "passive"))
    )
    (net (code "59") (name "Net-(U1-P3.2{slash}INT0{slash}SCLK_4{slash}I2CSCL_4{slash}PWMETI{slash}PWMETI2)") (class "Default")
      (node (ref "R59") (pin "2") (pinfunction "2_2") (pintype "passive"))
      (node (ref "U1") (pin "15") (pinfunction "P3.2/INT0/SCLK_4/I2CSCL_4/PWMETI/PWMETI2_15") (pintype "passive"))
    )
    (net (code "60") (name "Net-(U1-P5.4{slash}RST{slash}MCLKO{slash}PWM6_2)") (class "Default")
      (node (ref "R56") (pin "2") (pinfunction "2_2") (pintype "passive"))
      (node (ref "U1") (pin "9") (pinfunction "P5.4/RST/MCLKO/PWM6_2_9") (pintype "passive"))
    )
    (net (code "61") (name "Net-(U2-A)") (class "Default")
      (node (ref "R40") (pin "2") (pinfunction "2_2") (pintype "passive"))
      (node (ref "U2") (pin "4") (pinfunction "A_4") (pintype "passive"))
    )
    (net (code "62") (name "Net-(U2-B1)") (class "Default")
      (node (ref "R39") (pin "1") (pinfunction "1_1") (pintype "passive"))
      (node (ref "U2") (pin "3") (pinfunction "B1_3") (pintype "passive"))
    )
    (net (code "63") (name "Net-(U2-B2)") (class "Default")
      (node (ref "R41") (pin "1") (pinfunction "1_1") (pintype "passive"))
      (node (ref "U2") (pin "1") (pinfunction "B2_1") (pintype "passive"))
    )
    (net (code "64") (name "Net-(VD3-K)") (class "Default")
      (node (ref "R38") (pin "2") (pinfunction "2_2") (pintype "passive"))
      (node (ref "VD3") (pin "2") (pinfunction "K_2") (pintype "passive"))
    )
    (net (code "65") (name "VCC-5V") (class "Default")
      (node (ref "C49") (pin "2") (pinfunction "2_2") (pintype "passive"))
      (node (ref "C50") (pin "2") (pinfunction "2_2") (pintype "passive"))
      (node (ref "IC3") (pin "4") (pinfunction "V-_4") (pintype "power_in"))
      (node (ref "IC4") (pin "4") (pinfunction "V-_4") (pintype "power_in"))
      (node (ref "IC6") (pin "4") (pinfunction "V-_4") (pintype "power_in"))
      (node (ref "V2") (pin "3") (pinfunction "Vout_3") (pintype "passive"))
    )
    (net (code "66") (name "VCC-12V") (class "Default")
      (node (ref "C47") (pin "2") (pinfunction "2_2") (pintype "passive"))
      (node (ref "C48") (pin "2") (pinfunction "2_2") (pintype "passive"))
      (node (ref "IC9") (pin "4") (pinfunction "VSS_4") (pintype "passive"))
      (node (ref "JDC1") (pin "4") (pinfunction "4_4") (pintype "passive"))
      (node (ref "V2") (pin "2") (pinfunction "Vin_2") (pintype "passive"))
    )
    (net (code "67") (name "VCC5V") (class "Default")
      (node (ref "C1") (pin "2") (pinfunction "2_2") (pintype "passive"))
      (node (ref "C24") (pin "2") (pinfunction "2_2") (pintype "passive"))
      (node (ref "C25") (pin "2") (pinfunction "2_2") (pintype "passive"))
      (node (ref "C30") (pin "2") (pinfunction "2_2") (pintype "passive"))
      (node (ref "C45") (pin "2") (pinfunction "2_2") (pintype "passive"))
      (node (ref "C46") (pin "2") (pinfunction "2_2") (pintype "passive"))
      (node (ref "IC1") (pin "8") (pinfunction "VCC_8") (pintype "passive"))
      (node (ref "IC12") (pin "2") (pinfunction "VCC_2") (pintype "passive"))
      (node (ref "IC3") (pin "8") (pinfunction "V+_8") (pintype "power_in"))
      (node (ref "IC4") (pin "8") (pinfunction "V+_8") (pintype "power_in"))
      (node (ref "IC6") (pin "8") (pinfunction "V+_8") (pintype "power_in"))
      (node (ref "JP8") (pin "4") (pinfunction "4_4") (pintype "passive"))
      (node (ref "R1") (pin "2") (pinfunction "2_2") (pintype "passive"))
      (node (ref "R29") (pin "2") (pinfunction "2_2") (pintype "passive"))
      (node (ref "R51") (pin "2") (pinfunction "2_2") (pintype "passive"))
      (node (ref "R57") (pin "2") (pinfunction "2_2") (pintype "passive"))
      (node (ref "R59") (pin "1") (pinfunction "1_1") (pintype "passive"))
      (node (ref "R6") (pin "2") (pinfunction "2_2") (pintype "passive"))
      (node (ref "R61") (pin "2") (pinfunction "2_2") (pintype "passive"))
      (node (ref "R79") (pin "2") (pinfunction "2_2") (pintype "passive"))
      (node (ref "R80") (pin "2") (pinfunction "2_2") (pintype "passive"))
      (node (ref "R85") (pin "2") (pinfunction "2_2") (pintype "passive"))
      (node (ref "U1") (pin "10") (pinfunction "Vcc/AVcc_10") (pintype "passive"))
      (node (ref "U1") (pin "11") (pinfunction "ADC_VRef+_11") (pintype "passive"))
      (node (ref "U2") (pin "5") (pinfunction "VCC_5") (pintype "power_in"))
      (node (ref "U3") (pin "5") (pinfunction "VCC_5") (pintype "power_in"))
      (node (ref "U4") (pin "5") (pinfunction "VCC_5") (pintype "power_in"))
      (node (ref "V1") (pin "3") (pinfunction "Vout_3") (pintype "passive"))
    )
    (net (code "68") (name "VCC12V") (class "Default")
      (node (ref "C43") (pin "2") (pinfunction "2_2") (pintype "passive"))
      (node (ref "C44") (pin "2") (pinfunction "2_2") (pintype "passive"))
      (node (ref "IC9") (pin "6") (pinfunction "VDD_6") (pintype "passive"))
      (node (ref "JDC1") (pin "2") (pinfunction "2_2") (pintype "passive"))
      (node (ref "JP7") (pin "3") (pinfunction "3_3") (pintype "passive"))
      (node (ref "JP7") (pin "4") (pinfunction "4_4") (pintype "passive"))
      (node (ref "R53") (pin "2") (pinfunction "2_2") (pintype "passive"))
      (node (ref "R58") (pin "2") (pinfunction "2_2") (pintype "passive"))
      (node (ref "V1") (pin "1") (pinfunction "Vin_1") (pintype "passive"))
    )
    (net (code "69") (name "unconnected-(IC3B-OUT-Pad7)") (class "Default")
      (node (ref "IC3") (pin "7") (pinfunction "OUT_7") (pintype "output"))
    )
    (net (code "70") (name "unconnected-(IC9-NC-Pad2)") (class "Default")
      (node (ref "IC9") (pin "2") (pinfunction "NC_2") (pintype "passive"))
    )
    (net (code "71") (name "unconnected-(IC12-~{PFO}-Pad5)") (class "Default")
      (node (ref "IC12") (pin "5") (pinfunction "~{PFO}_5") (pintype "passive"))
    )
    (net (code "72") (name "unconnected-(JP6-Pad2)") (class "Default")
      (node (ref "JP6") (pin "2") (pinfunction "2_2") (pintype "passive"))
    )
    (net (code "73") (name "unconnected-(U1-P3.7{slash}INT3{slash}TxD_2{slash}CMP+-Pad20)") (class "Default")
      (node (ref "U1") (pin "20") (pinfunction "P3.7/INT3/TxD_2/CMP+_20") (pintype "passive"))
    )
    (net (code "74") (name "unconnected-(U1-PWM3N_2{slash}I2CSCL_2{slash}SCLK_2{slash}P2.5-Pad26)") (class "Default")
      (node (ref "U1") (pin "26") (pinfunction "PWM3N_2/I2CSCL_2/SCLK_2/P2.5_26") (pintype "passive"))
    )
    (net (code "75") (name "unconnected-(U1-PWM3P_2{slash}I2CSDA_2{slash}MISO_2{slash}P2.4-Pad25)") (class "Default")
      (node (ref "U1") (pin "25") (pinfunction "PWM3P_2/I2CSDA_2/MISO_2/P2.4_25") (pintype "passive"))
    )
    (net (code "76") (name "unconnected-(U1-PWM4N_2{slash}P2.7-Pad28)") (class "Default")
      (node (ref "U1") (pin "28") (pinfunction "PWM4N_2/P2.7_28") (pintype "passive"))
    )
    (net (code "77") (name "unconnected-(U1-PWM4P_2{slash}P2.6-Pad27)") (class "Default")
      (node (ref "U1") (pin "27") (pinfunction "PWM4P_2/P2.6_27") (pintype "passive"))
    )
    (net (code "78") (name "unconnected-(U1-T2CLKO{slash}MOSI{slash}PWM2N{slash}ADC3{slash}P1.3-Pad4)") (class "Default")
      (node (ref "U1") (pin "4") (pinfunction "T2CLKO/MOSI/PWM2N/ADC3/P1.3_4") (pintype "passive"))
    )
    (net (code "79") (name "unconnected-(U1-T3CLKO{slash}PWM6_3{slash}ADC9{slash}P0.1-Pad30)") (class "Default")
      (node (ref "U1") (pin "30") (pinfunction "T3CLKO/PWM6_3/ADC9/P0.1_30") (pintype "passive"))
    )
    (net (code "80") (name "unconnected-(U1-T3{slash}PWM5_3{slash}ADC8{slash}P0.0-Pad29)") (class "Default")
      (node (ref "U1") (pin "29") (pinfunction "T3/PWM5_3/ADC8/P0.0_29") (pintype "passive"))
    )
  )
)
